# Driver6.net
KiCad netlist of a schematic drawn in Altium Designer
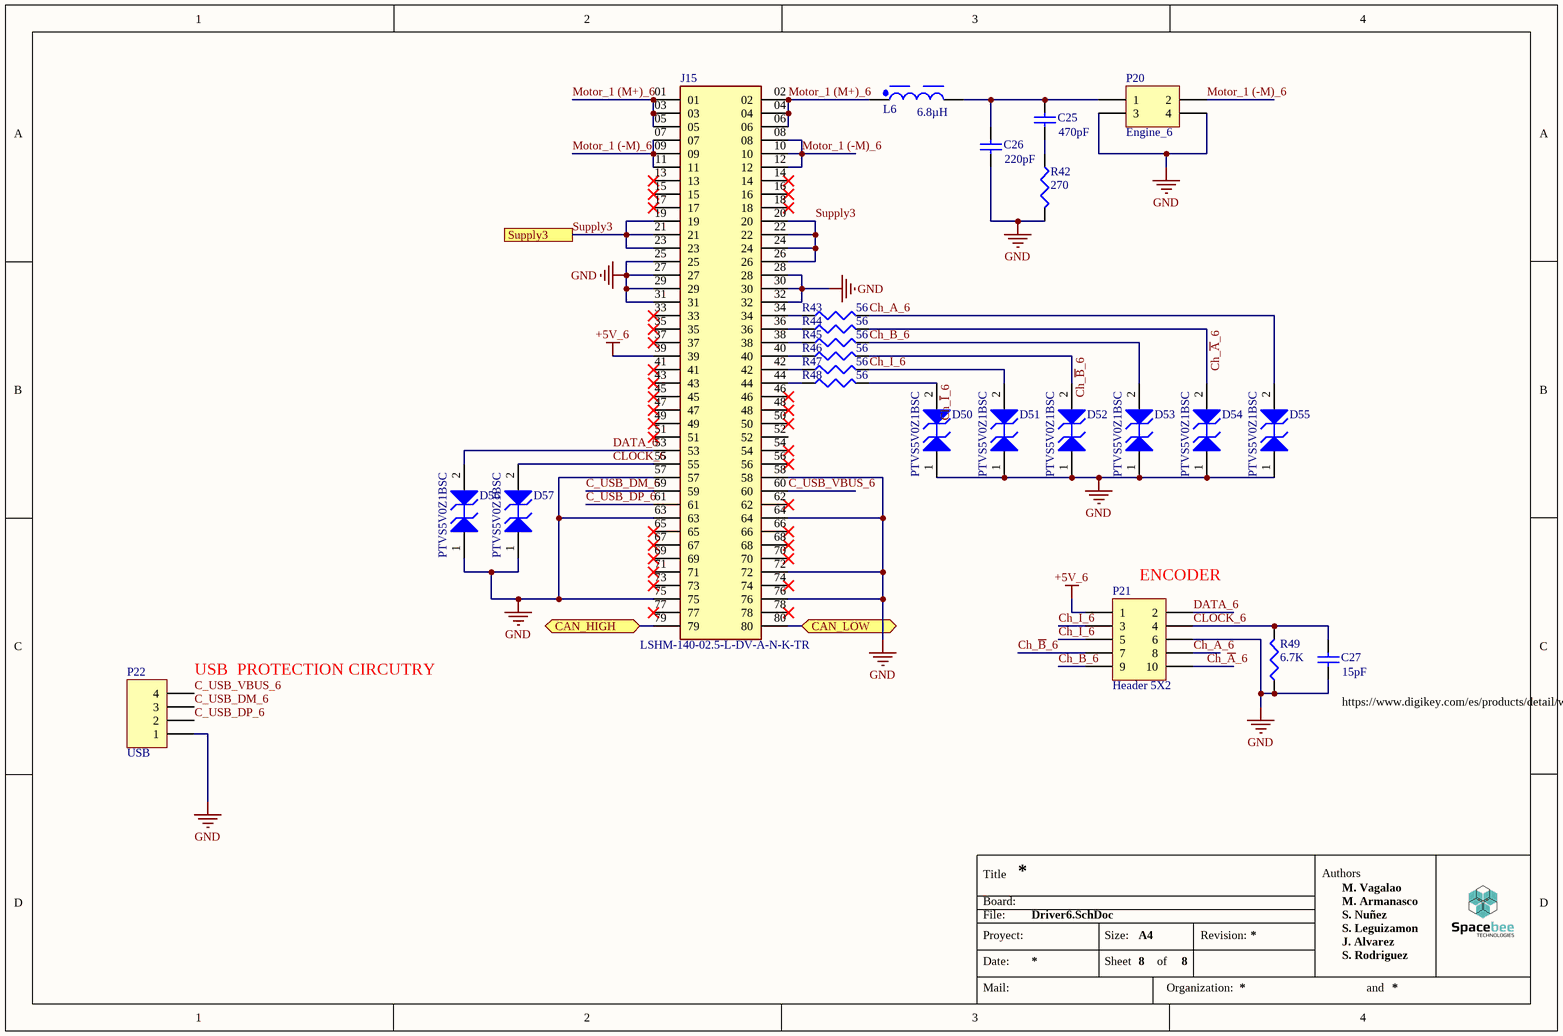
[diagram p0: Driver6.SchDoc]

(export (version "E")
  (design (tool "Eeschema 10.0.6"))
  (components
    (comp (ref "C25")
      (value "470pF")
      (footprint "1608[0603]")
      (description "Capacitor (Semiconductor SIM Model)")
      (fields (field (name "Comment") "Cap Semi") (field (name "PUBLISHER") "Altium Limited"))
      (libsource (lib "Miscellaneous Devices") (part "Cap Semi"))
    )
    (comp (ref "C26")
      (value "220pF")
      (footprint "1608[0603]")
      (description "Capacitor (Semiconductor SIM Model)")
      (fields (field (name "Comment") "Cap Semi") (field (name "PUBLISHER") "Altium Limited"))
      (libsource (lib "Miscellaneous Devices") (part "Cap Semi"))
    )
    (comp (ref "C27")
      (value "15pF")
      (footprint "1608[0603]")
      (description "Capacitor (Semiconductor SIM Model)")
      (fields (field (name "Comment") "Cap Semi") (field (name "PUBLISHER") "Altium Limited"))
      (libsource (lib "Miscellaneous Devices") (part "Cap Semi"))
    )
    (comp (ref "D50")
      (value "PTVS5V0Z1BSC")
      (footprint "SOD993B")
      (fields (field (name "MANUFACTURER") "On Semiconductor") (field (name "PARTNUMBER") "1SMB16CAT3"))
      (libsource (lib "DriverLib") (part "PTVS5V0Z1BSC"))
    )
    (comp (ref "D51")
      (value "PTVS5V0Z1BSC")
      (footprint "SOD993B")
      (fields (field (name "MANUFACTURER") "On Semiconductor") (field (name "PARTNUMBER") "1SMB16CAT3"))
      (libsource (lib "DriverLib") (part "PTVS5V0Z1BSC"))
    )
    (comp (ref "D52")
      (value "PTVS5V0Z1BSC")
      (footprint "SOD993B")
      (fields (field (name "MANUFACTURER") "On Semiconductor") (field (name "PARTNUMBER") "1SMB16CAT3"))
      (libsource (lib "DriverLib") (part "PTVS5V0Z1BSC"))
    )
    (comp (ref "D53")
      (value "PTVS5V0Z1BSC")
      (footprint "SOD993B")
      (fields (field (name "MANUFACTURER") "On Semiconductor") (field (name "PARTNUMBER") "1SMB16CAT3"))
      (libsource (lib "DriverLib") (part "PTVS5V0Z1BSC"))
    )
    (comp (ref "D54")
      (value "PTVS5V0Z1BSC")
      (footprint "SOD993B")
      (fields (field (name "MANUFACTURER") "On Semiconductor") (field (name "PARTNUMBER") "1SMB16CAT3"))
      (libsource (lib "DriverLib") (part "PTVS5V0Z1BSC"))
    )
    (comp (ref "D55")
      (value "PTVS5V0Z1BSC")
      (footprint "SOD993B")
      (fields (field (name "MANUFACTURER") "On Semiconductor") (field (name "PARTNUMBER") "1SMB16CAT3"))
      (libsource (lib "DriverLib") (part "PTVS5V0Z1BSC"))
    )
    (comp (ref "D56")
      (value "PTVS5V0Z1BSC")
      (footprint "SOD993B")
      (fields (field (name "MANUFACTURER") "On Semiconductor") (field (name "PARTNUMBER") "1SMB16CAT3"))
      (libsource (lib "DriverLib") (part "PTVS5V0Z1BSC"))
    )
    (comp (ref "D57")
      (value "PTVS5V0Z1BSC")
      (footprint "SOD993B")
      (fields (field (name "MANUFACTURER") "On Semiconductor") (field (name "PARTNUMBER") "1SMB16CAT3"))
      (libsource (lib "DriverLib") (part "PTVS5V0Z1BSC"))
    )
    (comp (ref "J15")
      (value "LSHM-140-02.5-L-DV-A-N-K-TR")
      (footprint "SAMTEC_LSHM-140-02.5-L-DV-A-N-K-TR")
      (description "LSHM - Samtec 0.50mm Razor Beam High-Speed Hermaphroditic Terminal / Socket Strip.")
      (libsource (lib "DriverLib") (part "LSHM-140-02.5-L-DV-A-N-K-TR"))
    )
    (comp (ref "L6")
      (value "6.8µH")
      (footprint "WE-XHMA_6060")
      (description "WE-XHMA SMD Power Inductor, size 1090, 6.8µH, 10.5A, 7.16mΩ")
      (fields
        (field (name "MANUFACTURER PART NUMBER") "78439369068")
        (field (name "MANUFACTURER") "Wurth Elektronik")
      )
      (libsource (lib "DriverLib") (part "78439369068"))
    )
    (comp (ref "P20")
      (value "Engine_6")
      (footprint "MOLEX_1724480004")
      (description "Header, 2-Pin, Dual row")
      (fields (field (name "PUBLISHER") "Altium Limited"))
      (libsource (lib "SpaceBee") (part "Header 2X2"))
    )
    (comp (ref "P21")
      (value "Header 5X2")
      (footprint "CONN_HIF3FC-14PA-2.54DS(71)_HIR")
      (description "Header, 5-Pin, Dual row")
      (fields (field (name "PUBLISHER") "Altium Limited"))
      (libsource (lib "DriverLib") (part "Header 5X2"))
    )
    (comp (ref "P22")
      (value "USB")
      (footprint "HDR1X4")
      (description "Header, 4-Pin")
      (fields (field (name "PUBLISHER") "Altium Limited"))
      (libsource (lib "Miscellaneous Connectors") (part "Header 4"))
    )
    (comp (ref "R42")
      (value "270")
      (footprint "J1-0603")
      (description "Resistor")
      (fields (field (name "Comment") "Res3") (field (name "PUBLISHER") "Altium Limited"))
      (libsource (lib "Miscellaneous Devices") (part "Res3"))
    )
    (comp (ref "R43")
      (value "56")
      (footprint "J1-0603")
      (description "Resistor")
      (fields (field (name "Comment") "Res3") (field (name "PUBLISHER") "Altium Limited"))
      (libsource (lib "Miscellaneous Devices") (part "Res3"))
    )
    (comp (ref "R44")
      (value "56")
      (footprint "J1-0603")
      (description "Resistor")
      (fields (field (name "Comment") "Res3") (field (name "PUBLISHER") "Altium Limited"))
      (libsource (lib "Miscellaneous Devices") (part "Res3"))
    )
    (comp (ref "R45")
      (value "56")
      (footprint "J1-0603")
      (description "Resistor")
      (fields (field (name "Comment") "Res3") (field (name "PUBLISHER") "Altium Limited"))
      (libsource (lib "Miscellaneous Devices") (part "Res3"))
    )
    (comp (ref "R46")
      (value "56")
      (footprint "J1-0603")
      (description "Resistor")
      (fields (field (name "Comment") "Res3") (field (name "PUBLISHER") "Altium Limited"))
      (libsource (lib "Miscellaneous Devices") (part "Res3"))
    )
    (comp (ref "R47")
      (value "56")
      (footprint "J1-0603")
      (description "Resistor")
      (fields (field (name "Comment") "Res3") (field (name "PUBLISHER") "Altium Limited"))
      (libsource (lib "Miscellaneous Devices") (part "Res3"))
    )
    (comp (ref "R48")
      (value "56")
      (footprint "J1-0603")
      (description "Resistor")
      (fields (field (name "Comment") "Res3") (field (name "PUBLISHER") "Altium Limited"))
      (libsource (lib "Miscellaneous Devices") (part "Res3"))
    )
    (comp (ref "R49")
      (value "6.7K")
      (footprint "J1-0603")
      (description "Resistor")
      (fields (field (name "Comment") "Res3") (field (name "PUBLISHER") "Altium Limited"))
      (libsource (lib "Miscellaneous Devices") (part "Res3"))
    )
  )
  (nets
    (net (code "1") (name "+5V_6") (class "Default")
      (node (ref "J15") (pin "39") (pinfunction "39_39") (pintype "passive"))
      (node (ref "P21") (pin "1") (pinfunction "1_1") (pintype "passive"))
    )
    (net (code "2") (name "/CAN_HIGH") (class "Default")
      (node (ref "J15") (pin "79") (pinfunction "79_79") (pintype "passive"))
    )
    (net (code "3") (name "/CAN_LOW") (class "Default")
      (node (ref "J15") (pin "80") (pinfunction "80_80") (pintype "passive"))
    )
    (net (code "4") (name "/CLOCK_6") (class "Default")
      (node (ref "C27") (pin "1") (pinfunction "1_1") (pintype "passive"))
      (node (ref "D57") (pin "2") (pinfunction "A2_2") (pintype "passive"))
      (node (ref "J15") (pin "55") (pinfunction "55_55") (pintype "passive"))
      (node (ref "P21") (pin "4") (pinfunction "4_4") (pintype "passive"))
      (node (ref "R49") (pin "2") (pinfunction "2_2") (pintype "passive"))
    )
    (net (code "5") (name "/C_USB_DM_6") (class "Default")
      (node (ref "J15") (pin "59") (pinfunction "59_59") (pintype "passive"))
      (node (ref "P22") (pin "3") (pinfunction "3_3") (pintype "passive"))
    )
    (net (code "6") (name "/C_USB_DP_6") (class "Default")
      (node (ref "J15") (pin "61") (pinfunction "61_61") (pintype "passive"))
      (node (ref "P22") (pin "2") (pinfunction "2_2") (pintype "passive"))
    )
    (net (code "7") (name "/C_USB_VBUS_6") (class "Default")
      (node (ref "J15") (pin "60") (pinfunction "60_60") (pintype "passive"))
      (node (ref "P22") (pin "4") (pinfunction "4_4") (pintype "passive"))
    )
    (net (code "8") (name "/Ch_A_6") (class "Default")
      (node (ref "D55") (pin "2") (pinfunction "A2_2") (pintype "passive"))
      (node (ref "P21") (pin "8") (pinfunction "8_8") (pintype "passive"))
      (node (ref "R43") (pin "2") (pinfunction "2_2") (pintype "passive"))
    )
    (net (code "9") (name "/Ch_B_6") (class "Default")
      (node (ref "D53") (pin "2") (pinfunction "A2_2") (pintype "passive"))
      (node (ref "P21") (pin "9") (pinfunction "9_9") (pintype "passive"))
      (node (ref "R45") (pin "2") (pinfunction "2_2") (pintype "passive"))
    )
    (net (code "10") (name "/Ch_I_6") (class "Default")
      (node (ref "D51") (pin "2") (pinfunction "A2_2") (pintype "passive"))
      (node (ref "P21") (pin "5") (pinfunction "5_5") (pintype "passive"))
      (node (ref "R47") (pin "2") (pinfunction "2_2") (pintype "passive"))
    )
    (net (code "11") (name "/Ch_~{A}_6") (class "Default")
      (node (ref "D54") (pin "2") (pinfunction "A2_2") (pintype "passive"))
      (node (ref "P21") (pin "10") (pinfunction "10_10") (pintype "passive"))
      (node (ref "R44") (pin "2") (pinfunction "2_2") (pintype "passive"))
    )
    (net (code "12") (name "/Ch_~{B}_6") (class "Default")
      (node (ref "D52") (pin "2") (pinfunction "A2_2") (pintype "passive"))
      (node (ref "P21") (pin "7") (pinfunction "7_7") (pintype "passive"))
      (node (ref "R46") (pin "2") (pinfunction "2_2") (pintype "passive"))
    )
    (net (code "13") (name "/Ch_~{I}_6") (class "Default")
      (node (ref "D50") (pin "2") (pinfunction "A2_2") (pintype "passive"))
      (node (ref "P21") (pin "3") (pinfunction "3_3") (pintype "passive"))
      (node (ref "R48") (pin "2") (pinfunction "2_2") (pintype "passive"))
    )
    (net (code "14") (name "/DATA_6") (class "Default")
      (node (ref "D56") (pin "2") (pinfunction "A2_2") (pintype "passive"))
      (node (ref "J15") (pin "53") (pinfunction "53_53") (pintype "passive"))
      (node (ref "P21") (pin "2") (pinfunction "2_2") (pintype "passive"))
    )
    (net (code "15") (name "/Motor_1 (-M)_6") (class "Default")
      (node (ref "J15") (pin "07") (pinfunction "07_07") (pintype "passive"))
      (node (ref "J15") (pin "08") (pinfunction "08_08") (pintype "passive"))
      (node (ref "J15") (pin "09") (pinfunction "09_09") (pintype "passive"))
      (node (ref "J15") (pin "10") (pinfunction "10_10") (pintype "passive"))
      (node (ref "J15") (pin "11") (pinfunction "11_11") (pintype "passive"))
      (node (ref "J15") (pin "12") (pinfunction "12_12") (pintype "passive"))
      (node (ref "P20") (pin "2") (pinfunction "2_2") (pintype "passive"))
    )
    (net (code "16") (name "/Motor_1 (M+)_6") (class "Default")
      (node (ref "J15") (pin "01") (pinfunction "01_01") (pintype "passive"))
      (node (ref "J15") (pin "02") (pinfunction "02_02") (pintype "passive"))
      (node (ref "J15") (pin "03") (pinfunction "03_03") (pintype "passive"))
      (node (ref "J15") (pin "04") (pinfunction "04_04") (pintype "passive"))
      (node (ref "J15") (pin "05") (pinfunction "05_05") (pintype "passive"))
      (node (ref "J15") (pin "06") (pinfunction "06_06") (pintype "passive"))
      (node (ref "L6") (pin "1") (pinfunction "1_1") (pintype "passive"))
    )
    (net (code "17") (name "/Supply3") (class "Default")
      (node (ref "J15") (pin "19") (pinfunction "19_19") (pintype "passive"))
      (node (ref "J15") (pin "20") (pinfunction "20_20") (pintype "passive"))
      (node (ref "J15") (pin "21") (pinfunction "21_21") (pintype "passive"))
      (node (ref "J15") (pin "22") (pinfunction "22_22") (pintype "passive"))
      (node (ref "J15") (pin "23") (pinfunction "23_23") (pintype "passive"))
      (node (ref "J15") (pin "24") (pinfunction "24_24") (pintype "passive"))
      (node (ref "J15") (pin "26") (pinfunction "26_26") (pintype "passive"))
    )
    (net (code "18") (name "GND") (class "Default")
      (node (ref "C26") (pin "2") (pinfunction "2_2") (pintype "passive"))
      (node (ref "C27") (pin "2") (pinfunction "2_2") (pintype "passive"))
      (node (ref "D50") (pin "1") (pinfunction "A1_1") (pintype "passive"))
      (node (ref "D51") (pin "1") (pinfunction "A1_1") (pintype "passive"))
      (node (ref "D52") (pin "1") (pinfunction "A1_1") (pintype "passive"))
      (node (ref "D53") (pin "1") (pinfunction "A1_1") (pintype "passive"))
      (node (ref "D54") (pin "1") (pinfunction "A1_1") (pintype "passive"))
      (node (ref "D55") (pin "1") (pinfunction "A1_1") (pintype "passive"))
      (node (ref "D56") (pin "1") (pinfunction "A1_1") (pintype "passive"))
      (node (ref "D57") (pin "1") (pinfunction "A1_1") (pintype "passive"))
      (node (ref "J15") (pin "25") (pinfunction "25_25") (pintype "passive"))
      (node (ref "J15") (pin "27") (pinfunction "27_27") (pintype "passive"))
      (node (ref "J15") (pin "28") (pinfunction "28_28") (pintype "passive"))
      (node (ref "J15") (pin "29") (pinfunction "29_29") (pintype "passive"))
      (node (ref "J15") (pin "30") (pinfunction "30_30") (pintype "passive"))
      (node (ref "J15") (pin "31") (pinfunction "31_31") (pintype "passive"))
      (node (ref "J15") (pin "32") (pinfunction "32_32") (pintype "passive"))
      (node (ref "J15") (pin "57") (pinfunction "57_57") (pintype "passive"))
      (node (ref "J15") (pin "58") (pinfunction "58_58") (pintype "passive"))
      (node (ref "J15") (pin "63") (pinfunction "63_63") (pintype "passive"))
      (node (ref "J15") (pin "64") (pinfunction "64_64") (pintype "passive"))
      (node (ref "J15") (pin "72") (pinfunction "72_72") (pintype "passive"))
      (node (ref "J15") (pin "75") (pinfunction "75_75") (pintype "passive"))
      (node (ref "J15") (pin "76") (pinfunction "76_76") (pintype "passive"))
      (node (ref "P20") (pin "3") (pinfunction "3_3") (pintype "passive"))
      (node (ref "P20") (pin "4") (pinfunction "4_4") (pintype "passive"))
      (node (ref "P21") (pin "6") (pinfunction "6_6") (pintype "passive"))
      (node (ref "P22") (pin "1") (pinfunction "1_1") (pintype "passive"))
      (node (ref "R42") (pin "2") (pinfunction "2_2") (pintype "passive"))
      (node (ref "R49") (pin "1") (pinfunction "1_1") (pintype "passive"))
    )
    (net (code "19") (name "Net-(C25-Pad1)") (class "Default")
      (node (ref "C25") (pin "1") (pinfunction "1_1") (pintype "passive"))
      (node (ref "C26") (pin "1") (pinfunction "1_1") (pintype "passive"))
      (node (ref "L6") (pin "2") (pinfunction "2_2") (pintype "passive"))
      (node (ref "P20") (pin "1") (pinfunction "1_1") (pintype "passive"))
    )
    (net (code "20") (name "Net-(C25-Pad2)") (class "Default")
      (node (ref "C25") (pin "2") (pinfunction "2_2") (pintype "passive"))
      (node (ref "R42") (pin "1") (pinfunction "1_1") (pintype "passive"))
    )
    (net (code "21") (name "Net-(J15-Pad34)") (class "Default")
      (node (ref "J15") (pin "34") (pinfunction "34_34") (pintype "passive"))
      (node (ref "R43") (pin "1") (pinfunction "1_1") (pintype "passive"))
    )
    (net (code "22") (name "Net-(J15-Pad36)") (class "Default")
      (node (ref "J15") (pin "36") (pinfunction "36_36") (pintype "passive"))
      (node (ref "R44") (pin "1") (pinfunction "1_1") (pintype "passive"))
    )
    (net (code "23") (name "Net-(J15-Pad38)") (class "Default")
      (node (ref "J15") (pin "38") (pinfunction "38_38") (pintype "passive"))
      (node (ref "R45") (pin "1") (pinfunction "1_1") (pintype "passive"))
    )
    (net (code "24") (name "Net-(J15-Pad40)") (class "Default")
      (node (ref "J15") (pin "40") (pinfunction "40_40") (pintype "passive"))
      (node (ref "R46") (pin "1") (pinfunction "1_1") (pintype "passive"))
    )
    (net (code "25") (name "Net-(J15-Pad42)") (class "Default")
      (node (ref "J15") (pin "42") (pinfunction "42_42") (pintype "passive"))
      (node (ref "R47") (pin "1") (pinfunction "1_1") (pintype "passive"))
    )
    (net (code "26") (name "Net-(J15-Pad44)") (class "Default")
      (node (ref "J15") (pin "44") (pinfunction "44_44") (pintype "passive"))
      (node (ref "R48") (pin "1") (pinfunction "1_1") (pintype "passive"))
    )
    (net (code "27") (name "unconnected-(J15-Pad13)") (class "Default")
      (node (ref "J15") (pin "13") (pinfunction "13_13") (pintype "passive+no_connect"))
    )
    (net (code "28") (name "unconnected-(J15-Pad14)") (class "Default")
      (node (ref "J15") (pin "14") (pinfunction "14_14") (pintype "passive+no_connect"))
    )
    (net (code "29") (name "unconnected-(J15-Pad15)") (class "Default")
      (node (ref "J15") (pin "15") (pinfunction "15_15") (pintype "passive+no_connect"))
    )
    (net (code "30") (name "unconnected-(J15-Pad16)") (class "Default")
      (node (ref "J15") (pin "16") (pinfunction "16_16") (pintype "passive+no_connect"))
    )
    (net (code "31") (name "unconnected-(J15-Pad17)") (class "Default")
      (node (ref "J15") (pin "17") (pinfunction "17_17") (pintype "passive+no_connect"))
    )
    (net (code "32") (name "unconnected-(J15-Pad18)") (class "Default")
      (node (ref "J15") (pin "18") (pinfunction "18_18") (pintype "passive+no_connect"))
    )
    (net (code "33") (name "unconnected-(J15-Pad33)") (class "Default")
      (node (ref "J15") (pin "33") (pinfunction "33_33") (pintype "passive+no_connect"))
    )
    (net (code "34") (name "unconnected-(J15-Pad35)") (class "Default")
      (node (ref "J15") (pin "35") (pinfunction "35_35") (pintype "passive+no_connect"))
    )
    (net (code "35") (name "unconnected-(J15-Pad37)") (class "Default")
      (node (ref "J15") (pin "37") (pinfunction "37_37") (pintype "passive+no_connect"))
    )
    (net (code "36") (name "unconnected-(J15-Pad41)") (class "Default")
      (node (ref "J15") (pin "41") (pinfunction "41_41") (pintype "passive+no_connect"))
    )
    (net (code "37") (name "unconnected-(J15-Pad43)") (class "Default")
      (node (ref "J15") (pin "43") (pinfunction "43_43") (pintype "passive+no_connect"))
    )
    (net (code "38") (name "unconnected-(J15-Pad45)") (class "Default")
      (node (ref "J15") (pin "45") (pinfunction "45_45") (pintype "passive+no_connect"))
    )
    (net (code "39") (name "unconnected-(J15-Pad46)") (class "Default")
      (node (ref "J15") (pin "46") (pinfunction "46_46") (pintype "passive+no_connect"))
    )
    (net (code "40") (name "unconnected-(J15-Pad47)") (class "Default")
      (node (ref "J15") (pin "47") (pinfunction "47_47") (pintype "passive+no_connect"))
    )
    (net (code "41") (name "unconnected-(J15-Pad48)") (class "Default")
      (node (ref "J15") (pin "48") (pinfunction "48_48") (pintype "passive+no_connect"))
    )
    (net (code "42") (name "unconnected-(J15-Pad49)") (class "Default")
      (node (ref "J15") (pin "49") (pinfunction "49_49") (pintype "passive+no_connect"))
    )
    (net (code "43") (name "unconnected-(J15-Pad50)") (class "Default")
      (node (ref "J15") (pin "50") (pinfunction "50_50") (pintype "passive+no_connect"))
    )
    (net (code "44") (name "unconnected-(J15-Pad51)") (class "Default")
      (node (ref "J15") (pin "51") (pinfunction "51_51") (pintype "passive+no_connect"))
    )
    (net (code "45") (name "unconnected-(J15-Pad52)") (class "Default")
      (node (ref "J15") (pin "52") (pinfunction "52_52") (pintype "passive"))
    )
    (net (code "46") (name "unconnected-(J15-Pad54)") (class "Default")
      (node (ref "J15") (pin "54") (pinfunction "54_54") (pintype "passive+no_connect"))
    )
    (net (code "47") (name "unconnected-(J15-Pad56)") (class "Default")
      (node (ref "J15") (pin "56") (pinfunction "56_56") (pintype "passive+no_connect"))
    )
    (net (code "48") (name "unconnected-(J15-Pad62)") (class "Default")
      (node (ref "J15") (pin "62") (pinfunction "62_62") (pintype "passive+no_connect"))
    )
    (net (code "49") (name "unconnected-(J15-Pad65)") (class "Default")
      (node (ref "J15") (pin "65") (pinfunction "65_65") (pintype "passive+no_connect"))
    )
    (net (code "50") (name "unconnected-(J15-Pad66)") (class "Default")
      (node (ref "J15") (pin "66") (pinfunction "66_66") (pintype "passive+no_connect"))
    )
    (net (code "51") (name "unconnected-(J15-Pad67)") (class "Default")
      (node (ref "J15") (pin "67") (pinfunction "67_67") (pintype "passive+no_connect"))
    )
    (net (code "52") (name "unconnected-(J15-Pad68)") (class "Default")
      (node (ref "J15") (pin "68") (pinfunction "68_68") (pintype "passive+no_connect"))
    )
    (net (code "53") (name "unconnected-(J15-Pad69)") (class "Default")
      (node (ref "J15") (pin "69") (pinfunction "69_69") (pintype "passive+no_connect"))
    )
    (net (code "54") (name "unconnected-(J15-Pad70)") (class "Default")
      (node (ref "J15") (pin "70") (pinfunction "70_70") (pintype "passive+no_connect"))
    )
    (net (code "55") (name "unconnected-(J15-Pad71)") (class "Default")
      (node (ref "J15") (pin "71") (pinfunction "71_71") (pintype "passive+no_connect"))
    )
    (net (code "56") (name "unconnected-(J15-Pad73)") (class "Default")
      (node (ref "J15") (pin "73") (pinfunction "73_73") (pintype "passive+no_connect"))
    )
    (net (code "57") (name "unconnected-(J15-Pad74)") (class "Default")
      (node (ref "J15") (pin "74") (pinfunction "74_74") (pintype "passive+no_connect"))
    )
    (net (code "58") (name "unconnected-(J15-Pad77)") (class "Default")
      (node (ref "J15") (pin "77") (pinfunction "77_77") (pintype "passive+no_connect"))
    )
    (net (code "59") (name "unconnected-(J15-Pad78)") (class "Default")
      (node (ref "J15") (pin "78") (pinfunction "78_78") (pintype "passive+no_connect"))
    )
  )
)
